# BLDCV1.net
KiCad netlist of a schematic drawn in Altium Designer
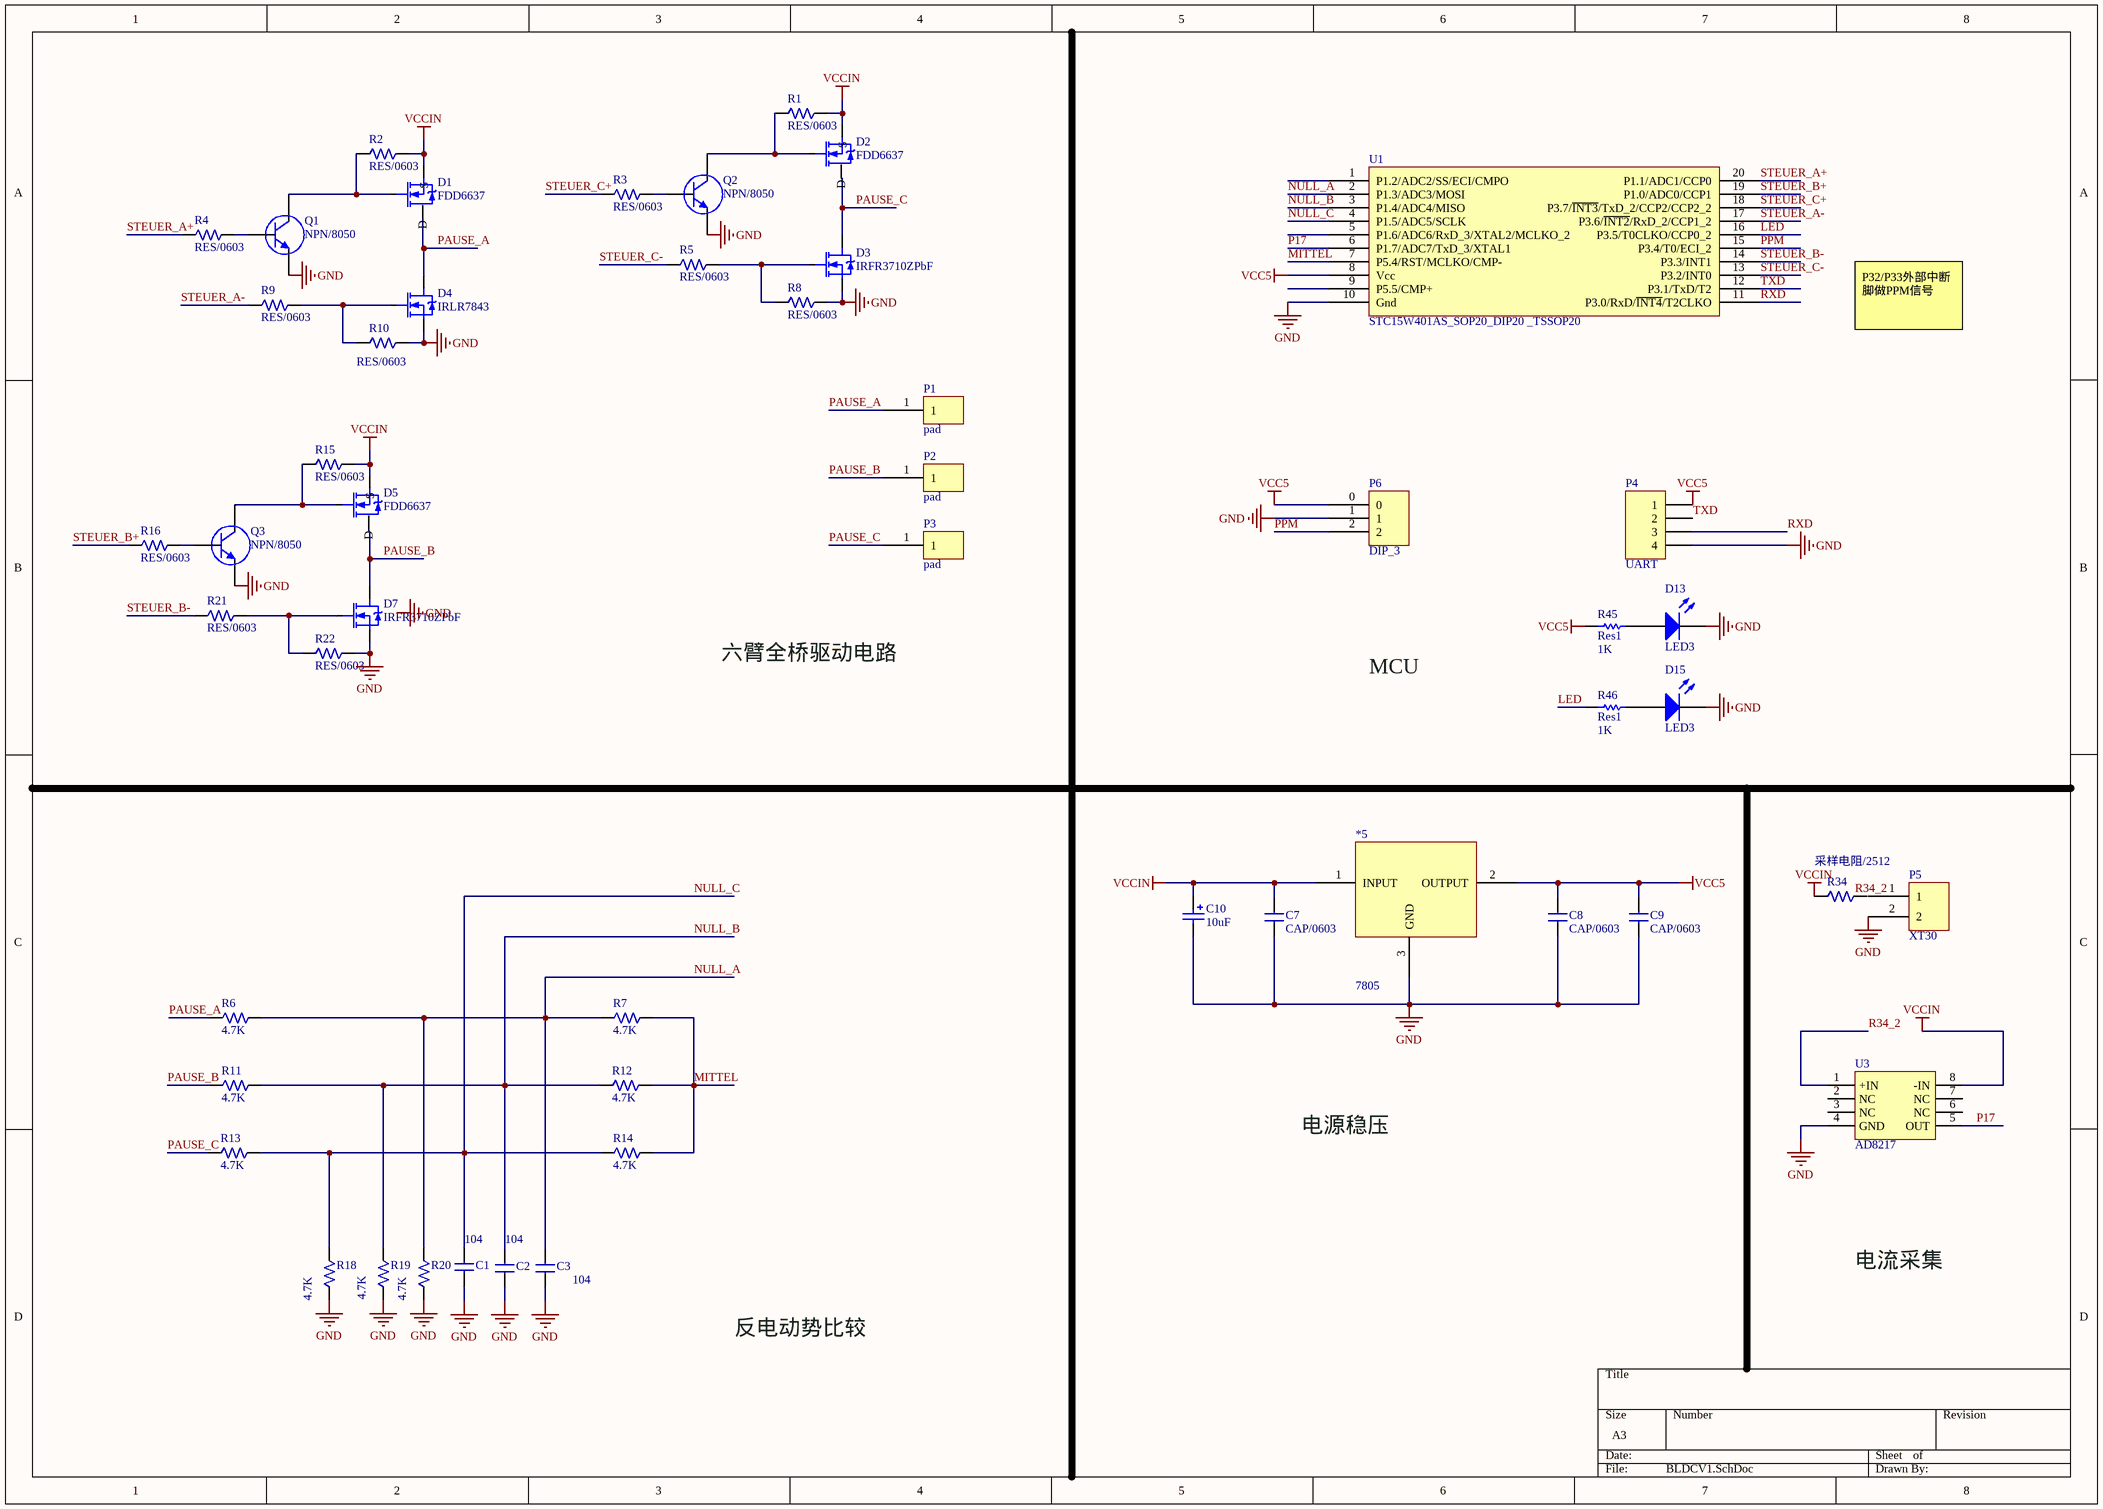
[diagram p0: BLDCV1.SchDoc]

(export (version "E")
  (design (tool "Eeschema 10.0.6"))
  (components
    (comp (ref "*5")
      (value "7805")
      (footprint "IRFR3710ZPbF_D-Pak")
      (libsource (lib "LJ_Integrated_Library") (part "7805"))
    )
    (comp (ref "C1")
      (value "104")
      (footprint "0603")
      (libsource (lib "LJ_Integrated_Library") (part "CAP/0603"))
    )
    (comp (ref "C2")
      (value "104")
      (footprint "0603")
      (libsource (lib "LJ_Integrated_Library") (part "CAP/0603"))
    )
    (comp (ref "C3")
      (value "104")
      (footprint "0603")
      (libsource (lib "LJ_Integrated_Library") (part "CAP/0603"))
    )
    (comp (ref "C7")
      (value "CAP/0603")
      (footprint "LED_DIP")
      (libsource (lib "LJ_Integrated_Library") (part "CAP/0603"))
    )
    (comp (ref "C8")
      (value "CAP/0603")
      (footprint "LC-0603_C")
      (libsource (lib "LJ_Integrated_Library") (part "CAP/0603"))
    )
    (comp (ref "C9")
      (value "CAP/0603")
      (footprint "LED_DIP")
      (libsource (lib "LJ_Integrated_Library") (part "CAP/0603"))
    )
    (comp (ref "C10")
      (value "10uF")
      (footprint "贴片铝电解6.3mm(16V 220U)")
      (description "Polarized Capacitor (Radial)")
      (fields (field (name "PUBLISHER") "Altium Limited"))
      (libsource (lib "LJ_Integrated_Library") (part "Cap Pol1"))
    )
    (comp (ref "D1")
      (value "FDD6637")
      (footprint "IRFR3710ZPbF_D-Pak")
      (libsource (lib "LJ_Integrated_Library") (part "FDD6637"))
    )
    (comp (ref "D2")
      (value "FDD6637")
      (footprint "IRFR3710ZPbF_D-Pak")
      (libsource (lib "LJ_Integrated_Library") (part "FDD6637"))
    )
    (comp (ref "D3")
      (value "IRFR3710ZPbF")
      (footprint "IRFR3710ZPbF_D-Pak")
      (libsource (lib "LJ_Integrated_Library") (part "IRFR3710ZPbF"))
    )
    (comp (ref "D4")
      (value "IRLR7843")
      (footprint "IRFR3710ZPbF_D-Pak")
      (libsource (lib "LJ_Integrated_Library") (part "IRFR3710ZPbF"))
    )
    (comp (ref "D5")
      (value "FDD6637")
      (footprint "IRFR3710ZPbF_D-Pak")
      (libsource (lib "LJ_Integrated_Library") (part "FDD6637"))
    )
    (comp (ref "D7")
      (value "IRFR3710ZPbF")
      (footprint "IRFR3710ZPbF_D-Pak")
      (libsource (lib "LJ_Integrated_Library") (part "IRFR3710ZPbF"))
    )
    (comp (ref "D13")
      (value "LED3")
      (footprint "LC-0603_LED_S1")
      (description "Typical BLUE SiC LED")
      (fields (field (name "PUBLISHER") "Altium Limited"))
      (libsource (lib "Miscellaneous Devices") (part "LED3"))
    )
    (comp (ref "D15")
      (value "LED3")
      (footprint "LC-0603_LED_S1")
      (description "Typical BLUE SiC LED")
      (fields (field (name "PUBLISHER") "Altium Limited"))
      (libsource (lib "Miscellaneous Devices") (part "LED3"))
    )
    (comp (ref "P1") (value "pad") (footprint "PAD") (libsource (lib "LJ_Integrated_Library") (part "pad")))
    (comp (ref "P2") (value "pad") (footprint "PAD") (libsource (lib "LJ_Schlib") (part "pad")))
    (comp (ref "P3") (value "pad") (footprint "PAD") (libsource (lib "LJ_Integrated_Library") (part "pad")))
    (comp (ref "P4")
      (value "UART")
      (footprint "HDR1X4")
      (description "Header, 4-Pin")
      (fields (field (name "PUBLISHER") "Altium Limited"))
      (libsource (lib "Miscellaneous Connectors") (part "Header 4"))
    )
    (comp (ref "P5") (value "XT30") (footprint "电源口") (libsource (lib "2017_electric") (part "XT30")))
    (comp (ref "P6")
      (value "DIP_3")
      (footprint "DIP_3")
      (libsource (lib "LJ_Integrated_Library") (part "DIP_3"))
    )
    (comp (ref "Q1")
      (value "NPN/8050")
      (footprint "NPN/8050")
      (libsource (lib "LJ_Integrated_Library") (part "NPN/8050"))
    )
    (comp (ref "Q2")
      (value "NPN/8050")
      (footprint "NPN/8050")
      (libsource (lib "LJ_Integrated_Library") (part "NPN/8050"))
    )
    (comp (ref "Q3")
      (value "NPN/8050")
      (footprint "NPN/8050")
      (libsource (lib "LJ_Integrated_Library") (part "NPN/8050"))
    )
    (comp (ref "R1")
      (value "RES/0603")
      (footprint "0603")
      (libsource (lib "LJ_Integrated_Library") (part "RES/0603"))
    )
    (comp (ref "R2")
      (value "RES/0603")
      (footprint "0603")
      (libsource (lib "LJ_Integrated_Library") (part "RES/0603"))
    )
    (comp (ref "R3")
      (value "RES/0603")
      (footprint "0603")
      (libsource (lib "LJ_Integrated_Library") (part "RES/0603"))
    )
    (comp (ref "R4")
      (value "RES/0603")
      (footprint "0603")
      (libsource (lib "LJ_Integrated_Library") (part "RES/0603"))
    )
    (comp (ref "R5")
      (value "RES/0603")
      (footprint "0603")
      (libsource (lib "LJ_Integrated_Library") (part "RES/0603"))
    )
    (comp (ref "R6")
      (value "4.7K")
      (footprint "0603")
      (libsource (lib "LJ_Integrated_Library") (part "RES/0603"))
    )
    (comp (ref "R7")
      (value "4.7K")
      (footprint "0603")
      (libsource (lib "LJ_Integrated_Library") (part "RES/0603"))
    )
    (comp (ref "R8")
      (value "RES/0603")
      (footprint "0603")
      (libsource (lib "LJ_Integrated_Library") (part "RES/0603"))
    )
    (comp (ref "R9")
      (value "RES/0603")
      (footprint "0603")
      (libsource (lib "LJ_Integrated_Library") (part "RES/0603"))
    )
    (comp (ref "R10")
      (value "RES/0603")
      (footprint "0603")
      (libsource (lib "LJ_Integrated_Library") (part "RES/0603"))
    )
    (comp (ref "R11")
      (value "4.7K")
      (footprint "0603")
      (libsource (lib "LJ_Integrated_Library") (part "RES/0603"))
    )
    (comp (ref "R12")
      (value "4.7K")
      (footprint "0603")
      (libsource (lib "LJ_Integrated_Library") (part "RES/0603"))
    )
    (comp (ref "R13")
      (value "4.7K")
      (footprint "0603")
      (libsource (lib "LJ_Integrated_Library") (part "RES/0603"))
    )
    (comp (ref "R14")
      (value "4.7K")
      (footprint "0603")
      (libsource (lib "LJ_Integrated_Library") (part "RES/0603"))
    )
    (comp (ref "R15")
      (value "RES/0603")
      (footprint "0603")
      (libsource (lib "LJ_Integrated_Library") (part "RES/0603"))
    )
    (comp (ref "R16")
      (value "RES/0603")
      (footprint "0603")
      (libsource (lib "LJ_Integrated_Library") (part "RES/0603"))
    )
    (comp (ref "R18")
      (value "4.7K")
      (footprint "0603")
      (libsource (lib "LJ_Integrated_Library") (part "RES/0603"))
    )
    (comp (ref "R19")
      (value "4.7K")
      (footprint "0603")
      (libsource (lib "LJ_Integrated_Library") (part "RES/0603"))
    )
    (comp (ref "R20")
      (value "4.7K")
      (footprint "0603")
      (libsource (lib "LJ_Integrated_Library") (part "RES/0603"))
    )
    (comp (ref "R21")
      (value "RES/0603")
      (footprint "0603")
      (libsource (lib "LJ_Integrated_Library") (part "RES/0603"))
    )
    (comp (ref "R22")
      (value "RES/0603")
      (footprint "0603")
      (libsource (lib "LJ_Integrated_Library") (part "RES/0603"))
    )
    (comp (ref "R34")
      (value "采样电阻/2512")
      (footprint "2512")
      (libsource (lib "LJ_Integrated_Library") (part "RES/2512"))
    )
    (comp (ref "R45")
      (value "Res1")
      (footprint "LC-0603_R")
      (description "Resistor")
      (fields (field (name "ALTIUM_VALUE") "1K") (field (name "PUBLISHER") "Altium Limited"))
      (libsource (lib "Miscellaneous Devices") (part "Res1"))
    )
    (comp (ref "R46")
      (value "Res1")
      (footprint "LC-0603_R")
      (description "Resistor")
      (fields (field (name "ALTIUM_VALUE") "1K") (field (name "PUBLISHER") "Altium Limited"))
      (libsource (lib "Miscellaneous Devices") (part "Res1"))
    )
    (comp (ref "U1")
      (value "STC15W401AS_SOP20_DIP20 _TSSOP20")
      (footprint "TSSOP20")
      (libsource (lib "stcmcu_altium_lib") (part "STC15W401AS_SOP20_DIP20 _TSSOP20"))
    )
    (comp (ref "U3") (value "AD8217") (footprint "LC-MSOP-8") (libsource (lib "LJ_Schlib") (part "AD8217")))
  )
  (nets
    (net (code "1") (name "/LED") (class "Default")
      (node (ref "R46") (pin "1") (pinfunction "1_1") (pintype "passive"))
      (node (ref "U1") (pin "16") (pinfunction "P3.5/T0CLKO/CCP0_2_16") (pintype "passive"))
    )
    (net (code "2") (name "/MITTEL") (class "Default")
      (node (ref "R12") (pin "2") (pinfunction "2_2") (pintype "passive"))
      (node (ref "R14") (pin "2") (pinfunction "2_2") (pintype "passive"))
      (node (ref "R7") (pin "2") (pinfunction "2_2") (pintype "passive"))
      (node (ref "U1") (pin "7") (pinfunction "P5.4/RST/MCLKO/CMP-_7") (pintype "passive"))
    )
    (net (code "3") (name "/NULL_A") (class "Default")
      (node (ref "C3") (pin "2") (pinfunction "2_2") (pintype "passive"))
      (node (ref "R20") (pin "2") (pinfunction "2_2") (pintype "passive"))
      (node (ref "R6") (pin "2") (pinfunction "2_2") (pintype "passive"))
      (node (ref "R7") (pin "1") (pinfunction "1_1") (pintype "passive"))
      (node (ref "U1") (pin "2") (pinfunction "P1.3/ADC3/MOSI_2") (pintype "passive"))
    )
    (net (code "4") (name "/NULL_B") (class "Default")
      (node (ref "C2") (pin "2") (pinfunction "2_2") (pintype "passive"))
      (node (ref "R11") (pin "2") (pinfunction "2_2") (pintype "passive"))
      (node (ref "R12") (pin "1") (pinfunction "1_1") (pintype "passive"))
      (node (ref "R19") (pin "2") (pinfunction "2_2") (pintype "passive"))
      (node (ref "U1") (pin "3") (pinfunction "P1.4/ADC4/MISO_3") (pintype "passive"))
    )
    (net (code "5") (name "/NULL_C") (class "Default")
      (node (ref "C1") (pin "2") (pinfunction "2_2") (pintype "passive"))
      (node (ref "R13") (pin "2") (pinfunction "2_2") (pintype "passive"))
      (node (ref "R14") (pin "1") (pinfunction "1_1") (pintype "passive"))
      (node (ref "R18") (pin "2") (pinfunction "2_2") (pintype "passive"))
      (node (ref "U1") (pin "4") (pinfunction "P1.5/ADC5/SCLK_4") (pintype "passive"))
    )
    (net (code "6") (name "/P17") (class "Default")
      (node (ref "U1") (pin "6") (pinfunction "P1.7/ADC7/TxD_3/XTAL1_6") (pintype "passive"))
      (node (ref "U3") (pin "5") (pinfunction "OUT_5") (pintype "passive"))
    )
    (net (code "7") (name "/PAUSE_A") (class "Default")
      (node (ref "D1") (pin "3") (pinfunction "D_3") (pintype "passive"))
      (node (ref "D4") (pin "3") (pinfunction "D_3") (pintype "passive"))
      (node (ref "P1") (pin "1") (pinfunction "1_1") (pintype "passive"))
      (node (ref "R6") (pin "1") (pinfunction "1_1") (pintype "passive"))
    )
    (net (code "8") (name "/PAUSE_B") (class "Default")
      (node (ref "D5") (pin "3") (pinfunction "D_3") (pintype "passive"))
      (node (ref "D7") (pin "3") (pinfunction "D_3") (pintype "passive"))
      (node (ref "P2") (pin "1") (pinfunction "1_1") (pintype "passive"))
      (node (ref "R11") (pin "1") (pinfunction "1_1") (pintype "passive"))
    )
    (net (code "9") (name "/PAUSE_C") (class "Default")
      (node (ref "D2") (pin "3") (pinfunction "D_3") (pintype "passive"))
      (node (ref "D3") (pin "3") (pinfunction "D_3") (pintype "passive"))
      (node (ref "P3") (pin "1") (pinfunction "1_1") (pintype "passive"))
      (node (ref "R13") (pin "1") (pinfunction "1_1") (pintype "passive"))
    )
    (net (code "10") (name "/PPM") (class "Default")
      (node (ref "P6") (pin "2") (pinfunction "2_2") (pintype "passive"))
      (node (ref "U1") (pin "15") (pinfunction "P3.4/T0/ECI_2_15") (pintype "passive"))
    )
    (net (code "11") (name "/R34_2") (class "Default")
      (node (ref "U3") (pin "1") (pinfunction "+IN_1") (pintype "passive"))
    )
    (net (code "12") (name "/RXD") (class "Default")
      (node (ref "P4") (pin "3") (pinfunction "3_3") (pintype "passive"))
      (node (ref "U1") (pin "11") (pinfunction "P3.0/RxD/~{INT4}/T2CLKO_11") (pintype "passive"))
    )
    (net (code "13") (name "/STEUER_A+") (class "Default")
      (node (ref "R4") (pin "1") (pinfunction "1_1") (pintype "passive"))
      (node (ref "U1") (pin "20") (pinfunction "P1.1/ADC1/CCP0_20") (pintype "passive"))
    )
    (net (code "14") (name "/STEUER_A-") (class "Default")
      (node (ref "R9") (pin "1") (pinfunction "1_1") (pintype "passive"))
      (node (ref "U1") (pin "17") (pinfunction "P3.6/~{INT2}/RxD_2/CCP1_2_17") (pintype "passive"))
    )
    (net (code "15") (name "/STEUER_B+") (class "Default")
      (node (ref "R16") (pin "1") (pinfunction "1_1") (pintype "passive"))
      (node (ref "U1") (pin "19") (pinfunction "P1.0/ADC0/CCP1_19") (pintype "passive"))
    )
    (net (code "16") (name "/STEUER_B-") (class "Default")
      (node (ref "R21") (pin "1") (pinfunction "1_1") (pintype "passive"))
      (node (ref "U1") (pin "14") (pinfunction "P3.3/INT1_14") (pintype "passive"))
    )
    (net (code "17") (name "/STEUER_C+") (class "Default")
      (node (ref "R3") (pin "1") (pinfunction "1_1") (pintype "passive"))
      (node (ref "U1") (pin "18") (pinfunction "P3.7/~{INT3}/TxD_2/CCP2/CCP2_2_18") (pintype "passive"))
    )
    (net (code "18") (name "/STEUER_C-") (class "Default")
      (node (ref "R5") (pin "1") (pinfunction "1_1") (pintype "passive"))
      (node (ref "U1") (pin "13") (pinfunction "P3.2/INT0_13") (pintype "passive"))
    )
    (net (code "19") (name "/TXD") (class "Default")
      (node (ref "P4") (pin "2") (pinfunction "2_2") (pintype "passive"))
      (node (ref "U1") (pin "12") (pinfunction "P3.1/TxD/T2_12") (pintype "passive"))
    )
    (net (code "20") (name "GND") (class "Default")
      (node (ref "*5") (pin "3") (pinfunction "GND_3") (pintype "passive"))
      (node (ref "C1") (pin "1") (pinfunction "1_1") (pintype "passive"))
      (node (ref "C10") (pin "2") (pinfunction "2_2") (pintype "passive"))
      (node (ref "C2") (pin "1") (pinfunction "1_1") (pintype "passive"))
      (node (ref "C3") (pin "1") (pinfunction "1_1") (pintype "passive"))
      (node (ref "C7") (pin "1") (pinfunction "1_1") (pintype "passive"))
      (node (ref "C8") (pin "1") (pinfunction "1_1") (pintype "passive"))
      (node (ref "C9") (pin "1") (pinfunction "1_1") (pintype "passive"))
      (node (ref "D13") (pin "2") (pinfunction "K_2") (pintype "passive"))
      (node (ref "D15") (pin "2") (pinfunction "K_2") (pintype "passive"))
      (node (ref "D3") (pin "2") (pinfunction "S_2") (pintype "passive"))
      (node (ref "D4") (pin "2") (pinfunction "S_2") (pintype "passive"))
      (node (ref "D7") (pin "2") (pinfunction "S_2") (pintype "passive"))
      (node (ref "P4") (pin "4") (pinfunction "4_4") (pintype "passive"))
      (node (ref "P5") (pin "2") (pinfunction "2_2") (pintype "passive"))
      (node (ref "P6") (pin "1") (pinfunction "1_1") (pintype "passive"))
      (node (ref "Q1") (pin "2") (pinfunction "E_2") (pintype "passive"))
      (node (ref "Q2") (pin "2") (pinfunction "E_2") (pintype "passive"))
      (node (ref "Q3") (pin "2") (pinfunction "E_2") (pintype "passive"))
      (node (ref "R10") (pin "2") (pinfunction "2_2") (pintype "passive"))
      (node (ref "R18") (pin "1") (pinfunction "1_1") (pintype "passive"))
      (node (ref "R19") (pin "1") (pinfunction "1_1") (pintype "passive"))
      (node (ref "R20") (pin "1") (pinfunction "1_1") (pintype "passive"))
      (node (ref "R22") (pin "2") (pinfunction "2_2") (pintype "passive"))
      (node (ref "R8") (pin "2") (pinfunction "2_2") (pintype "passive"))
      (node (ref "U1") (pin "10") (pinfunction "Gnd_10") (pintype "passive"))
      (node (ref "U3") (pin "4") (pinfunction "GND_4") (pintype "passive"))
    )
    (net (code "21") (name "Net-(D1-G)") (class "Default")
      (node (ref "D1") (pin "1") (pinfunction "G_1") (pintype "passive"))
      (node (ref "Q1") (pin "3") (pinfunction "C_3") (pintype "passive"))
      (node (ref "R2") (pin "1") (pinfunction "1_1") (pintype "passive"))
    )
    (net (code "22") (name "Net-(D2-G)") (class "Default")
      (node (ref "D2") (pin "1") (pinfunction "G_1") (pintype "passive"))
      (node (ref "Q2") (pin "3") (pinfunction "C_3") (pintype "passive"))
      (node (ref "R1") (pin "1") (pinfunction "1_1") (pintype "passive"))
    )
    (net (code "23") (name "Net-(D3-G)") (class "Default")
      (node (ref "D3") (pin "1") (pinfunction "G_1") (pintype "passive"))
      (node (ref "R5") (pin "2") (pinfunction "2_2") (pintype "passive"))
      (node (ref "R8") (pin "1") (pinfunction "1_1") (pintype "passive"))
    )
    (net (code "24") (name "Net-(D4-G)") (class "Default")
      (node (ref "D4") (pin "1") (pinfunction "G_1") (pintype "passive"))
      (node (ref "R10") (pin "1") (pinfunction "1_1") (pintype "passive"))
      (node (ref "R9") (pin "2") (pinfunction "2_2") (pintype "passive"))
    )
    (net (code "25") (name "Net-(D5-G)") (class "Default")
      (node (ref "D5") (pin "1") (pinfunction "G_1") (pintype "passive"))
      (node (ref "Q3") (pin "3") (pinfunction "C_3") (pintype "passive"))
      (node (ref "R15") (pin "1") (pinfunction "1_1") (pintype "passive"))
    )
    (net (code "26") (name "Net-(D7-G)") (class "Default")
      (node (ref "D7") (pin "1") (pinfunction "G_1") (pintype "passive"))
      (node (ref "R21") (pin "2") (pinfunction "2_2") (pintype "passive"))
      (node (ref "R22") (pin "1") (pinfunction "1_1") (pintype "passive"))
    )
    (net (code "27") (name "Net-(D13-A)") (class "Default")
      (node (ref "D13") (pin "1") (pinfunction "A_1") (pintype "passive"))
      (node (ref "R45") (pin "2") (pinfunction "2_2") (pintype "passive"))
    )
    (net (code "28") (name "Net-(D15-A)") (class "Default")
      (node (ref "D15") (pin "1") (pinfunction "A_1") (pintype "passive"))
      (node (ref "R46") (pin "2") (pinfunction "2_2") (pintype "passive"))
    )
    (net (code "29") (name "Net-(Q1-B)") (class "Default")
      (node (ref "Q1") (pin "1") (pinfunction "B_1") (pintype "passive"))
      (node (ref "R4") (pin "2") (pinfunction "2_2") (pintype "passive"))
    )
    (net (code "30") (name "Net-(Q2-B)") (class "Default")
      (node (ref "Q2") (pin "1") (pinfunction "B_1") (pintype "passive"))
      (node (ref "R3") (pin "2") (pinfunction "2_2") (pintype "passive"))
    )
    (net (code "31") (name "Net-(Q3-B)") (class "Default")
      (node (ref "Q3") (pin "1") (pinfunction "B_1") (pintype "passive"))
      (node (ref "R16") (pin "2") (pinfunction "2_2") (pintype "passive"))
    )
    (net (code "32") (name "VCC5") (class "Default")
      (node (ref "*5") (pin "2") (pinfunction "OUTPUT_2") (pintype "passive"))
      (node (ref "C8") (pin "2") (pinfunction "2_2") (pintype "passive"))
      (node (ref "C9") (pin "2") (pinfunction "2_2") (pintype "passive"))
      (node (ref "P4") (pin "1") (pinfunction "1_1") (pintype "passive"))
      (node (ref "P6") (pin "0") (pinfunction "0_0") (pintype "passive"))
      (node (ref "R45") (pin "1") (pinfunction "1_1") (pintype "passive"))
      (node (ref "U1") (pin "8") (pinfunction "Vcc_8") (pintype "passive"))
    )
    (net (code "33") (name "VCCIN") (class "Default")
      (node (ref "*5") (pin "1") (pinfunction "INPUT_1") (pintype "passive"))
      (node (ref "C10") (pin "1") (pinfunction "1_1") (pintype "passive"))
      (node (ref "C7") (pin "2") (pinfunction "2_2") (pintype "passive"))
      (node (ref "D1") (pin "2") (pinfunction "S_2") (pintype "passive"))
      (node (ref "D2") (pin "2") (pinfunction "S_2") (pintype "passive"))
      (node (ref "D5") (pin "2") (pinfunction "S_2") (pintype "passive"))
      (node (ref "R1") (pin "2") (pinfunction "2_2") (pintype "passive"))
      (node (ref "R15") (pin "2") (pinfunction "2_2") (pintype "passive"))
      (node (ref "R2") (pin "2") (pinfunction "2_2") (pintype "passive"))
      (node (ref "R34") (pin "1") (pinfunction "1_1") (pintype "passive"))
      (node (ref "U3") (pin "8") (pinfunction "-IN_8") (pintype "passive"))
    )
    (net (code "34") (name "unconnected-(P5-Pad1)") (class "Default")
      (node (ref "P5") (pin "1") (pinfunction "1_1") (pintype "passive"))
    )
    (net (code "35") (name "unconnected-(R34-Pad2)") (class "Default")
      (node (ref "R34") (pin "2") (pinfunction "2_2") (pintype "passive"))
    )
    (net (code "36") (name "unconnected-(U1-P1.2{slash}ADC2{slash}SS{slash}ECI{slash}CMPO-Pad1)") (class "Default")
      (node (ref "U1") (pin "1") (pinfunction "P1.2/ADC2/SS/ECI/CMPO_1") (pintype "passive"))
    )
    (net (code "37") (name "unconnected-(U1-P1.6{slash}ADC6{slash}RxD_3{slash}XTAL2{slash}MCLKO_2-Pad5)") (class "Default")
      (node (ref "U1") (pin "5") (pinfunction "P1.6/ADC6/RxD_3/XTAL2/MCLKO_2_5") (pintype "passive"))
    )
    (net (code "38") (name "unconnected-(U1-P5.5{slash}CMP+-Pad9)") (class "Default")
      (node (ref "U1") (pin "9") (pinfunction "P5.5/CMP+_9") (pintype "passive"))
    )
    (net (code "39") (name "unconnected-(U3-NC-Pad2)") (class "Default")
      (node (ref "U3") (pin "2") (pinfunction "NC_2") (pintype "passive"))
    )
    (net (code "40") (name "unconnected-(U3-NC-Pad3)") (class "Default")
      (node (ref "U3") (pin "3") (pinfunction "NC_3") (pintype "passive"))
    )
    (net (code "41") (name "unconnected-(U3-NC-Pad6)") (class "Default")
      (node (ref "U3") (pin "6") (pinfunction "NC_6") (pintype "passive"))
    )
    (net (code "42") (name "unconnected-(U3-NC-Pad7)") (class "Default")
      (node (ref "U3") (pin "7") (pinfunction "NC_7") (pintype "passive"))
    )
  )
)
